# schematic.net
KiCad netlist of a schematic drawn in EasyEDA
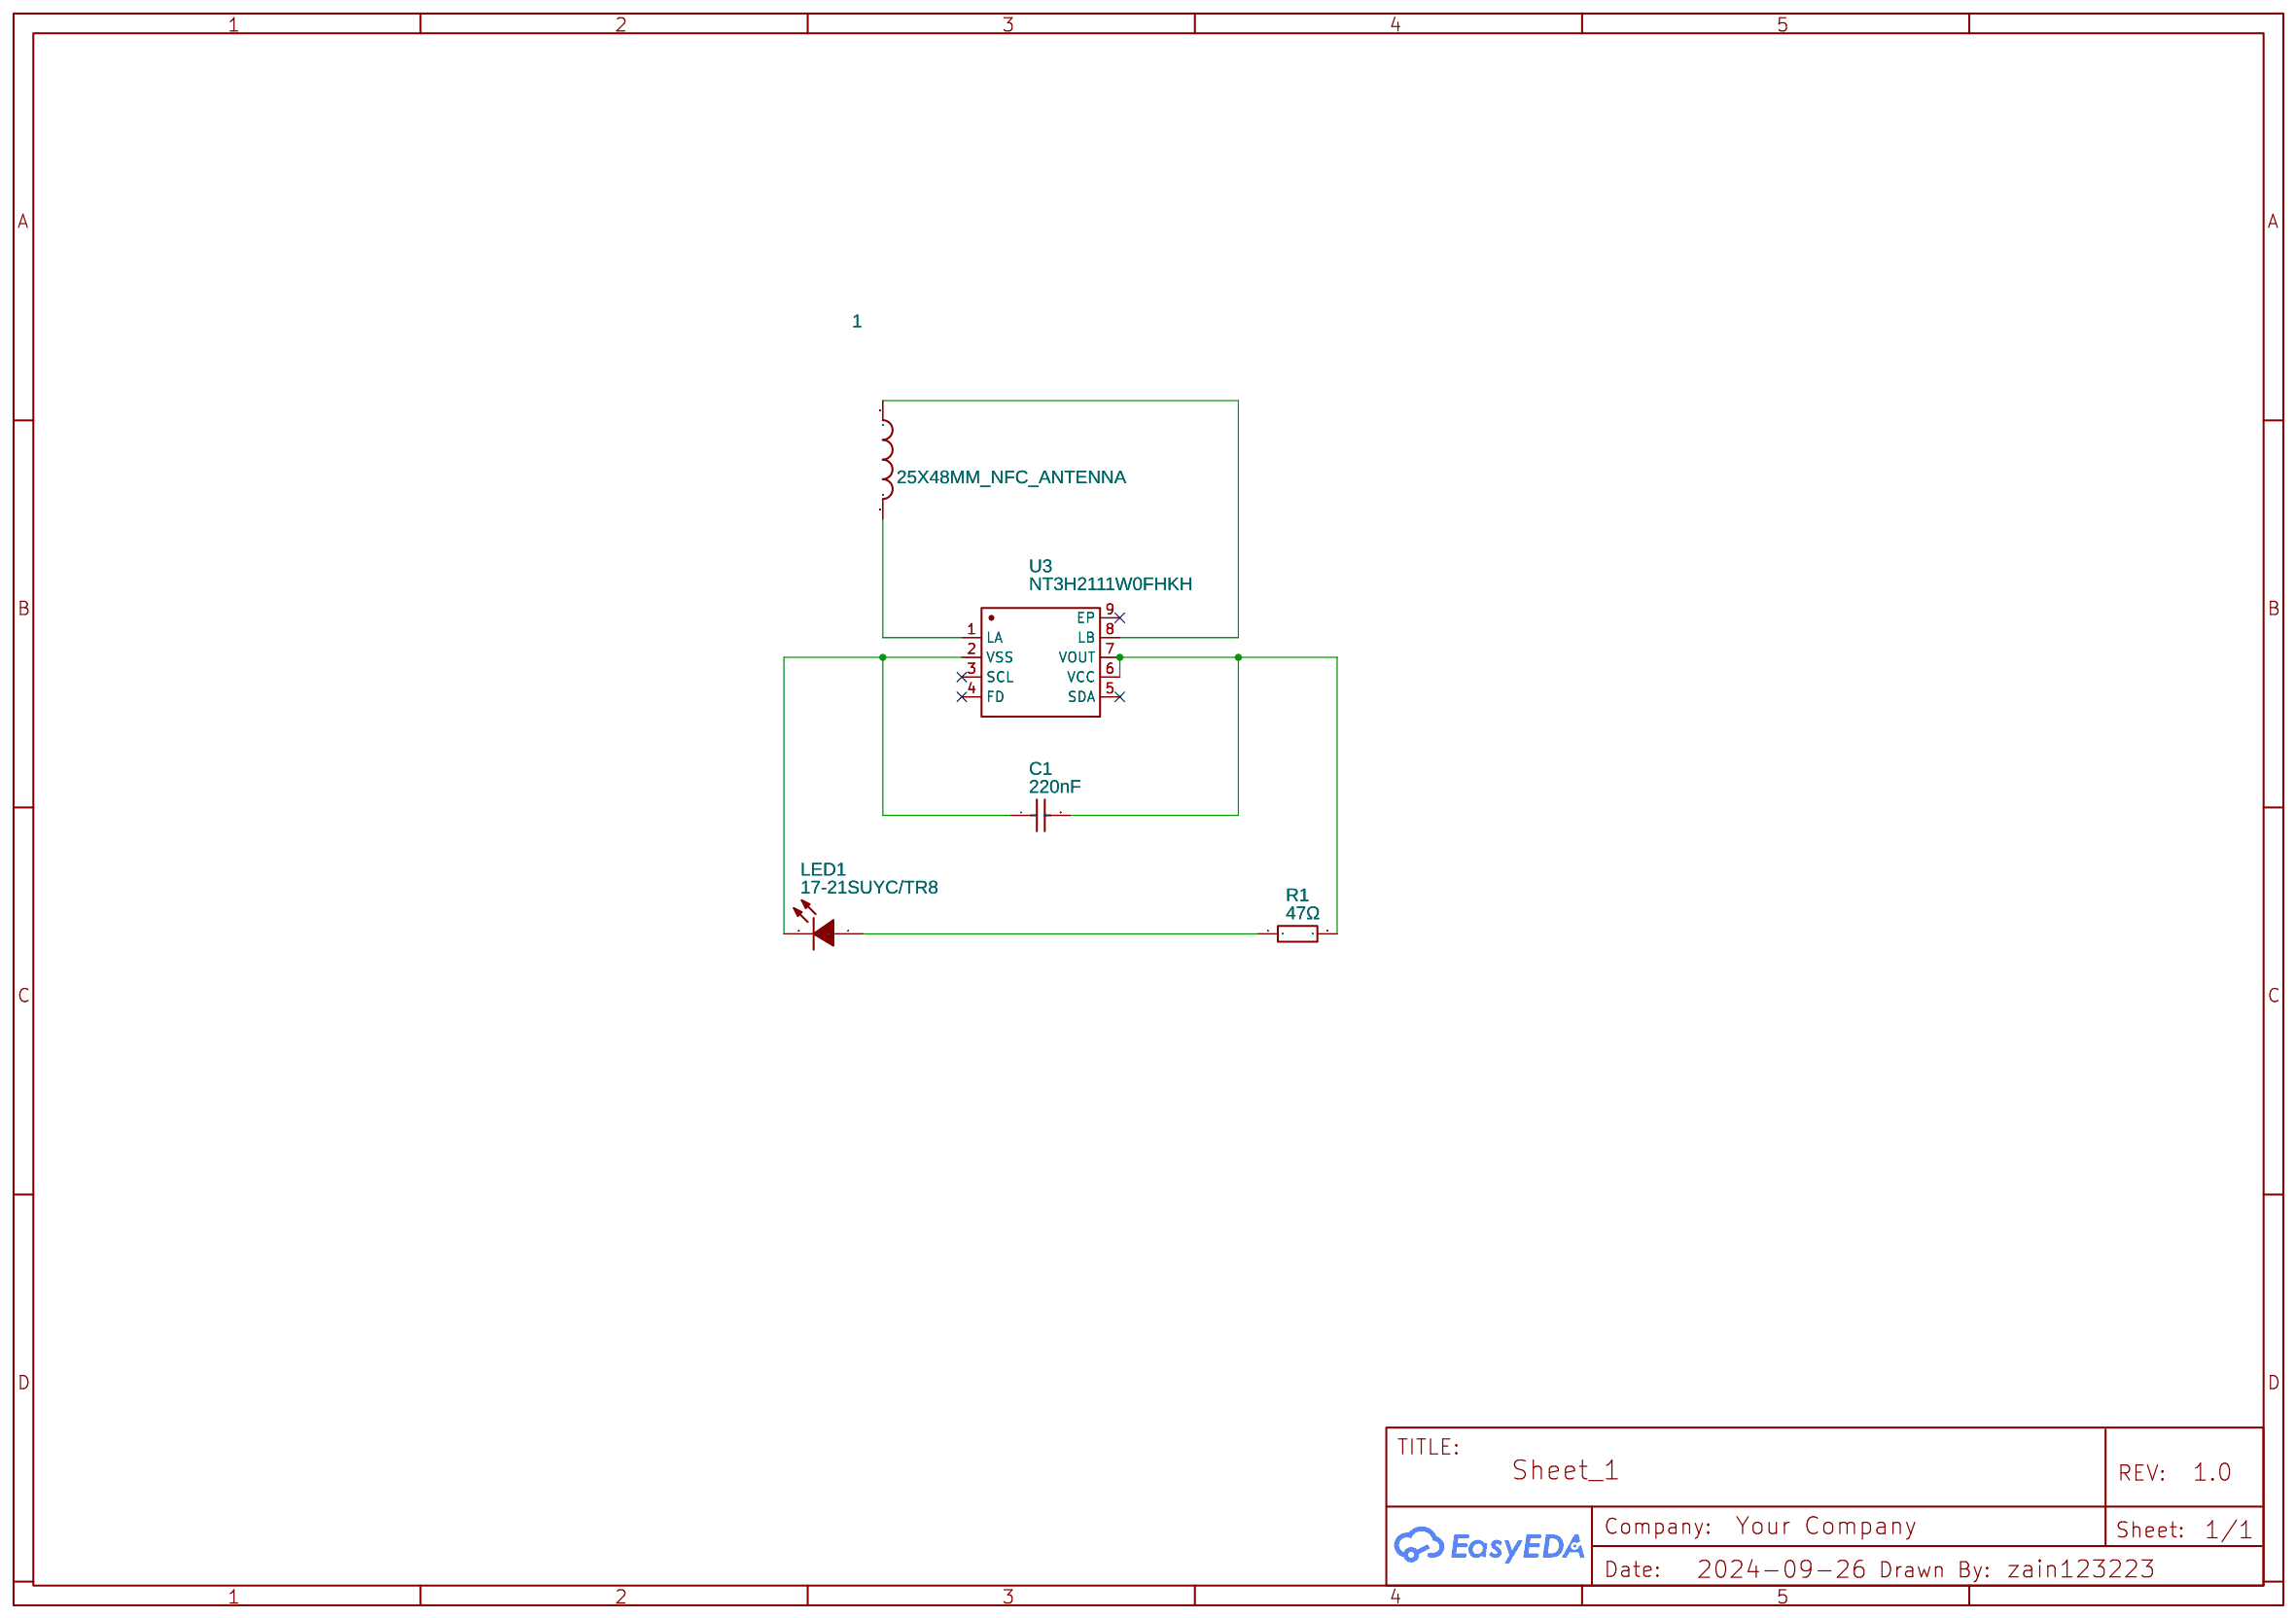
[diagram p0: schematic sheet]

(export (version "E")
  (design (tool "Eeschema 10.0.6"))
  (components
    (comp (ref "1") (value "25X48MM_NFC_ANTENNA") (libsource (lib "") (part "25X48MM_NFC_ANTENNA")))
    (comp (ref "C1")
      (value "220nF")
      (fields
        (field (name "Manufacturer Part") "CL10B224KA8NNNC")
        (field (name "Manufacturer") "SAMSUNG(三星)")
      )
      (libsource (lib "") (part "CL10B224KA8NNNC"))
    )
    (comp (ref "LED1")
      (value "17-21SUYC/TR8")
      (fields (field (name "Manufacturer Part") "KT-0805黄灯") (field (name "Manufacturer") "KENTO"))
      (libsource (lib "") (part "17-21SUYC/TR8"))
    )
    (comp (ref "R1")
      (value "47Ω")
      (fields
        (field (name "Manufacturer Part") "0603WAF470JT5E")
        (field (name "Manufacturer") "UNI-ROYAL(厚声)")
      )
      (libsource (lib "") (part "0603WAF470JT5E"))
    )
    (comp (ref "U3")
      (value "NT3H2111W0FHKH")
      (fields (field (name "Manufacturer") "NXP(恩智浦)"))
      (libsource (lib "") (part "NT3H2111W0FHKH"))
    )
  )
  (nets
    (net (code "1") (name "Net-(LED1-+)") (class "Default")
      (node (ref "LED1") (pin "1") (pinfunction "+_1") (pintype "unspecified"))
      (node (ref "R1") (pin "1") (pinfunction "1_1") (pintype "input"))
    )
    (net (code "2") (name "Net-(LED1--)") (class "Default")
      (node (ref "C1") (pin "1") (pinfunction "1_1") (pintype "input"))
      (node (ref "LED1") (pin "2") (pinfunction "-_2") (pintype "unspecified"))
      (node (ref "U3") (pin "2") (pinfunction "VSS_2") (pintype "unspecified"))
    )
    (net (code "3") (name "Net-(U3-LA)") (class "Default")
      (node (ref "1") (pin "P$2") (pinfunction "P$2_P$2") (pintype "bidirectional"))
      (node (ref "U3") (pin "1") (pinfunction "LA_1") (pintype "unspecified"))
    )
    (net (code "4") (name "Net-(U3-LB)") (class "Default")
      (node (ref "1") (pin "P$1") (pinfunction "P$1_P$1") (pintype "bidirectional"))
      (node (ref "U3") (pin "8") (pinfunction "LB_8") (pintype "unspecified"))
    )
    (net (code "5") (name "Net-(U3-VCC)") (class "Default")
      (node (ref "C1") (pin "2") (pinfunction "2_2") (pintype "input"))
      (node (ref "R1") (pin "2") (pinfunction "2_2") (pintype "input"))
      (node (ref "U3") (pin "6") (pinfunction "VCC_6") (pintype "unspecified"))
      (node (ref "U3") (pin "7") (pinfunction "VOUT_7") (pintype "unspecified"))
    )
    (net (code "6") (name "unconnected-(U3-EP-Pad9)") (class "Default")
      (node (ref "U3") (pin "9") (pinfunction "EP_9") (pintype "unspecified+no_connect"))
    )
    (net (code "7") (name "unconnected-(U3-FD-Pad4)") (class "Default")
      (node (ref "U3") (pin "4") (pinfunction "FD_4") (pintype "unspecified+no_connect"))
    )
    (net (code "8") (name "unconnected-(U3-SCL-Pad3)") (class "Default")
      (node (ref "U3") (pin "3") (pinfunction "SCL_3") (pintype "unspecified+no_connect"))
    )
    (net (code "9") (name "unconnected-(U3-SDA-Pad5)") (class "Default")
      (node (ref "U3") (pin "5") (pinfunction "SDA_5") (pintype "unspecified+no_connect"))
    )
  )
)
